# PHOTODIODE.net
KiCad netlist of a schematic drawn in Altium Designer
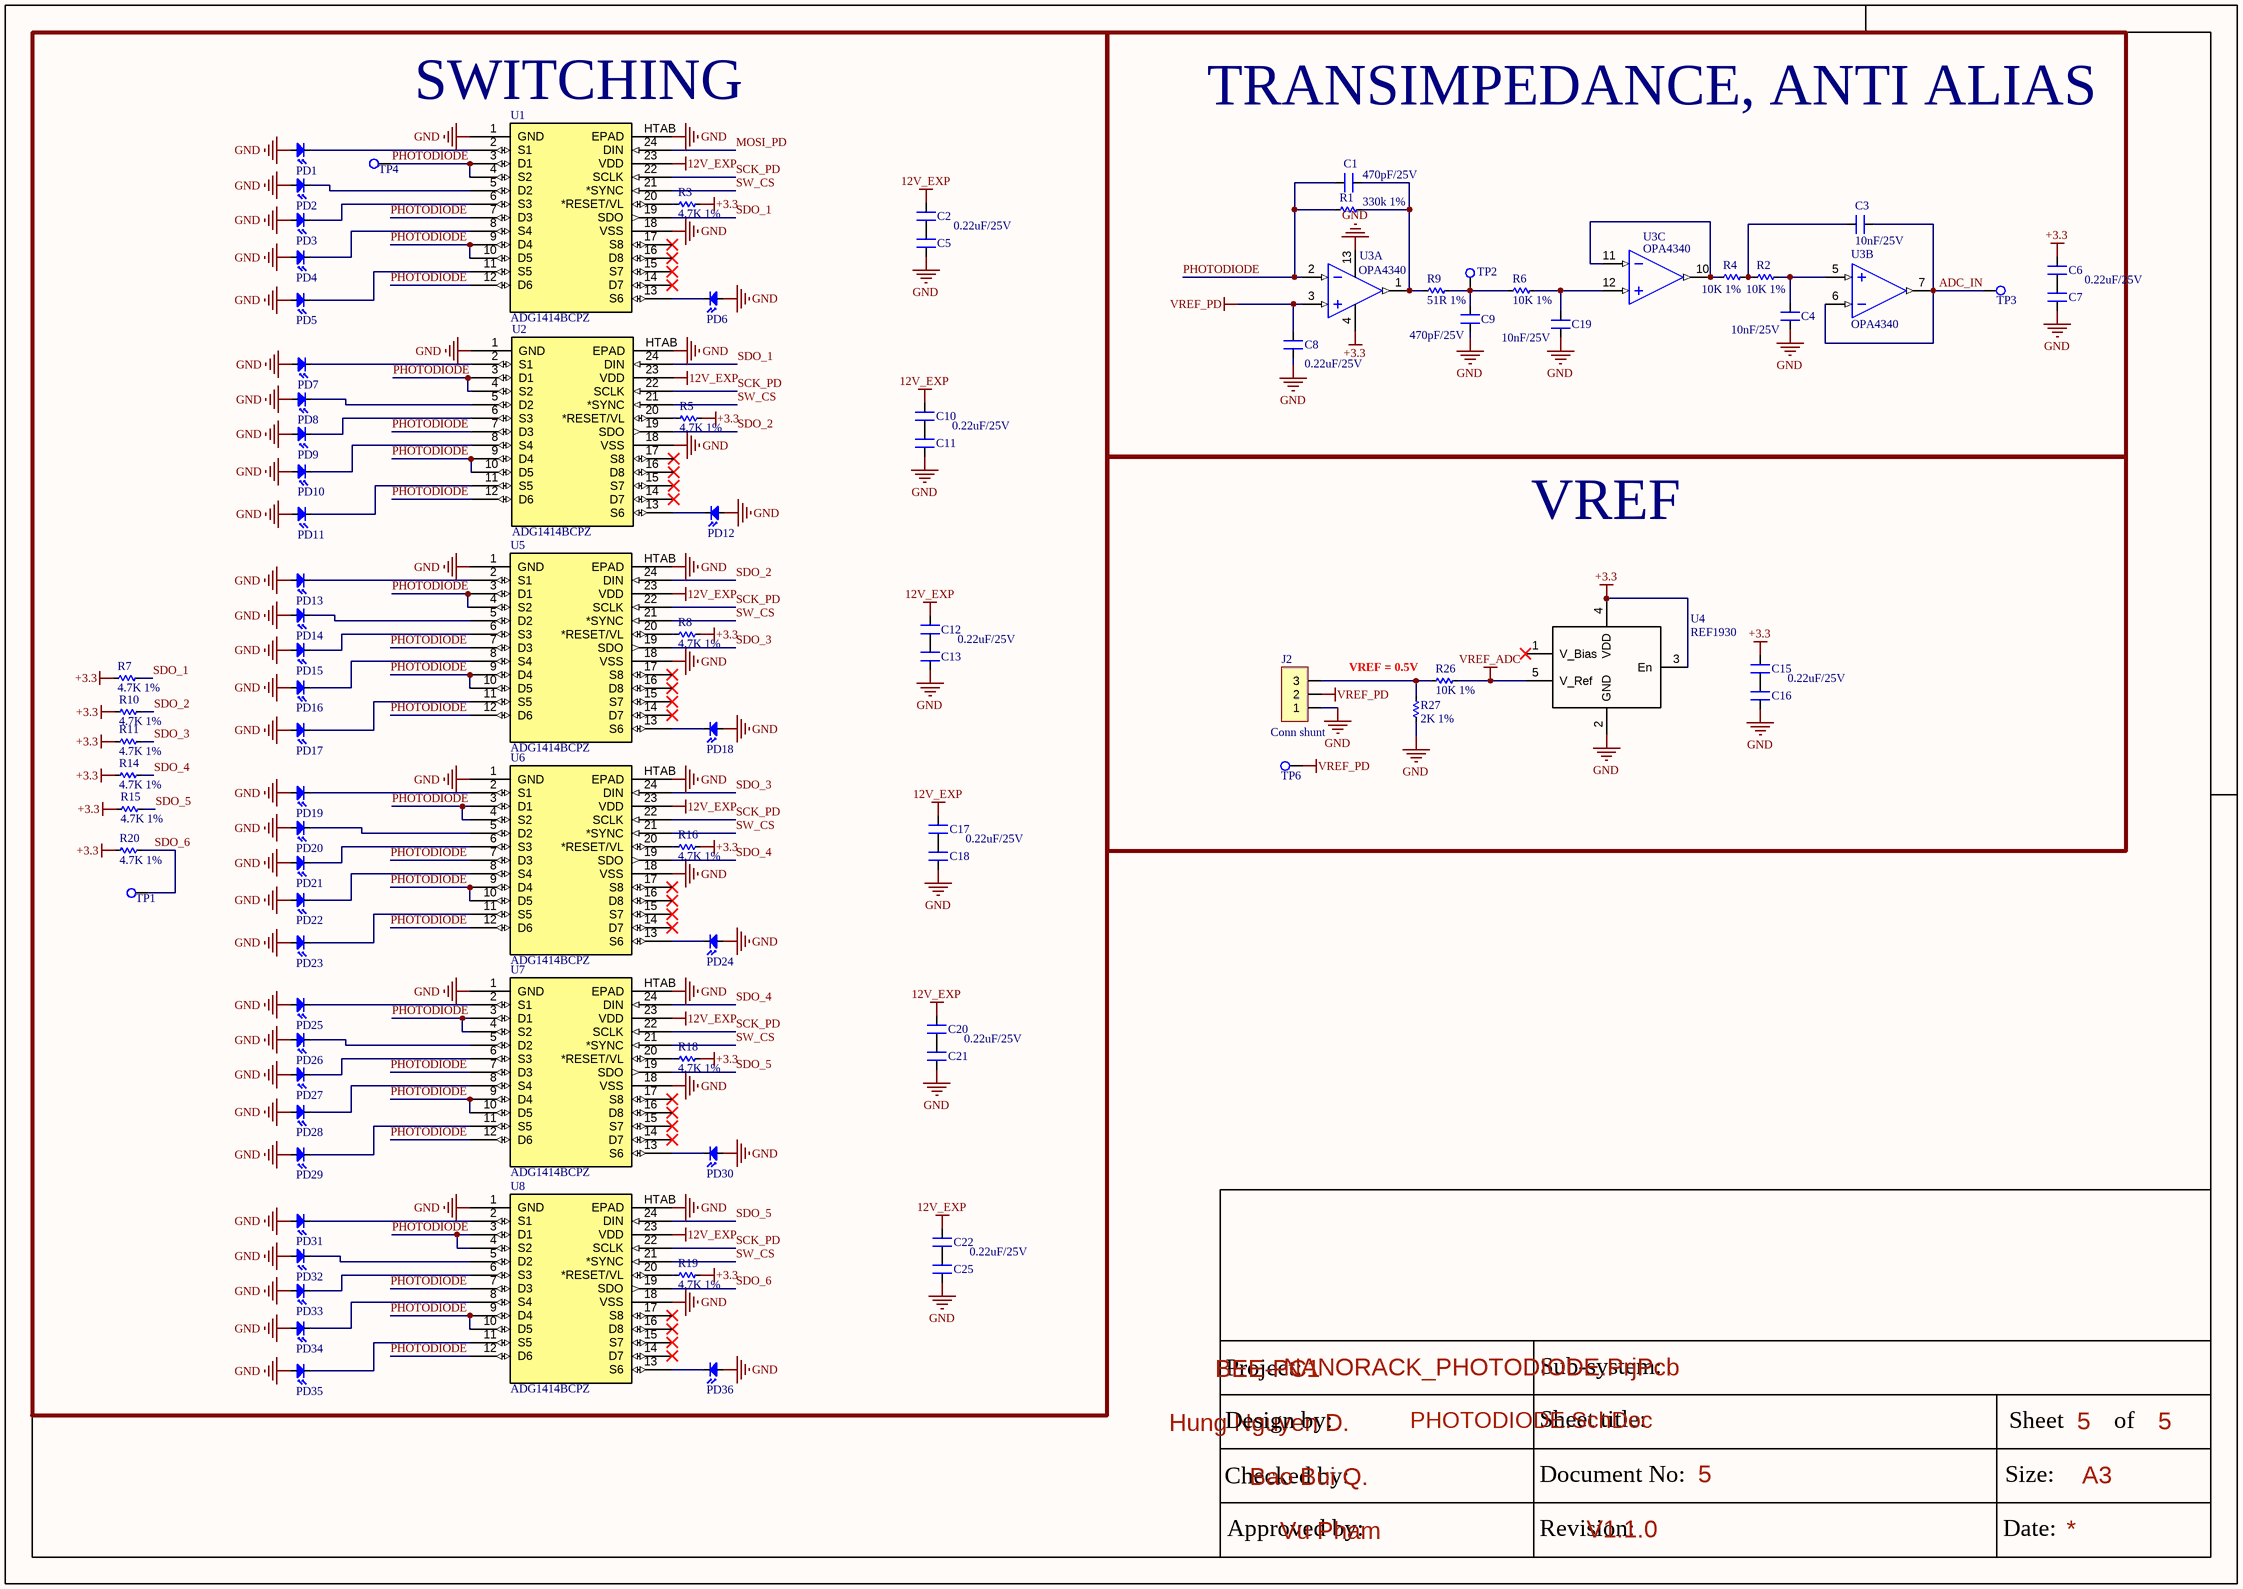
[diagram p0: PHOTODIODE.SchDoc]

(export (version "E")
  (design (tool "Eeschema 10.0.6"))
  (components
    (comp (ref "C1")
      (value "470pF/25V")
      (footprint "CN-SMD-0603")
      (description "0603")
      (libsource (lib "Capacitors") (part "CM"))
    )
    (comp (ref "C2")
      (value "0.22uF/25V")
      (footprint "CN-SMD-0603")
      (description "0603")
      (libsource (lib "Capacitors") (part "CM"))
    )
    (comp (ref "C3")
      (value "10nF/25V")
      (footprint "CN-SMD-0603")
      (description "0603")
      (libsource (lib "Capacitors") (part "CM"))
    )
    (comp (ref "C4")
      (value "10nF/25V")
      (footprint "CN-SMD-0603")
      (description "0603")
      (libsource (lib "Capacitors") (part "CM"))
    )
    (comp (ref "C5")
      (value "0.22uF/25V")
      (footprint "CN-SMD-0603")
      (description "0603")
      (libsource (lib "Capacitors") (part "CM"))
    )
    (comp (ref "C6")
      (value "0.22uF/25V")
      (footprint "CN-SMD-0603")
      (description "0603")
      (libsource (lib "Capacitors") (part "CM"))
    )
    (comp (ref "C7")
      (value "0.22uF/25V")
      (footprint "CN-SMD-0603")
      (description "0603")
      (libsource (lib "Capacitors") (part "CM"))
    )
    (comp (ref "C8")
      (value "0.22uF/25V")
      (footprint "CN-SMD-0603")
      (description "0603")
      (libsource (lib "Capacitors") (part "CM"))
    )
    (comp (ref "C9")
      (value "470pF/25V")
      (footprint "CN-SMD-0603")
      (description "0603")
      (libsource (lib "Capacitors") (part "CM"))
    )
    (comp (ref "C10")
      (value "0.22uF/25V")
      (footprint "CN-SMD-0603")
      (description "0603")
      (libsource (lib "Capacitors") (part "CM"))
    )
    (comp (ref "C11")
      (value "0.22uF/25V")
      (footprint "CN-SMD-0603")
      (description "0603")
      (libsource (lib "Capacitors") (part "CM"))
    )
    (comp (ref "C12")
      (value "0.22uF/25V")
      (footprint "CN-SMD-0603")
      (description "0603")
      (libsource (lib "Capacitors") (part "CM"))
    )
    (comp (ref "C13")
      (value "0.22uF/25V")
      (footprint "CN-SMD-0603")
      (description "0603")
      (libsource (lib "Capacitors") (part "CM"))
    )
    (comp (ref "C15")
      (value "0.22uF/25V")
      (footprint "CN-SMD-0603")
      (description "0603")
      (libsource (lib "Capacitors") (part "CM"))
    )
    (comp (ref "C16")
      (value "0.22uF/25V")
      (footprint "CN-SMD-0603")
      (description "0603")
      (libsource (lib "Capacitors") (part "CM"))
    )
    (comp (ref "C17")
      (value "0.22uF/25V")
      (footprint "CN-SMD-0603")
      (description "0603")
      (libsource (lib "Capacitors") (part "CM"))
    )
    (comp (ref "C18")
      (value "0.22uF/25V")
      (footprint "CN-SMD-0603")
      (description "0603")
      (libsource (lib "Capacitors") (part "CM"))
    )
    (comp (ref "C19")
      (value "10nF/25V")
      (footprint "CN-SMD-0603")
      (description "0603")
      (libsource (lib "Capacitors") (part "CM"))
    )
    (comp (ref "C20")
      (value "0.22uF/25V")
      (footprint "CN-SMD-0603")
      (description "0603")
      (libsource (lib "Capacitors") (part "CM"))
    )
    (comp (ref "C21")
      (value "0.22uF/25V")
      (footprint "CN-SMD-0603")
      (description "0603")
      (libsource (lib "Capacitors") (part "CM"))
    )
    (comp (ref "C22")
      (value "0.22uF/25V")
      (footprint "CN-SMD-0603")
      (description "0603")
      (libsource (lib "Capacitors") (part "CM"))
    )
    (comp (ref "C25")
      (value "0.22uF/25V")
      (footprint "CN-SMD-0603")
      (description "0603")
      (libsource (lib "Capacitors") (part "CM"))
    )
    (comp (ref "J2")
      (value "Conn shunt")
      (footprint "M50-3930342")
      (description "WR-PHD 2.54 mm Angled Socket Header")
      (fields
        (field (name "MANUFACTURER") "Würth Elektronik eiSos GmbH")
        (field (name "PARTNO") "613003143121")
        (field (name "CREATED BY") "Karrer Zheng")
      )
      (libsource (lib "Library") (part "JP3"))
    )
    (comp (ref "PD1")
      (value "Photodiode")
      (footprint "VEMD5080X01")
      (libsource (lib "Library_HUNG") (part "Photodiode"))
    )
    (comp (ref "PD2")
      (value "Photodiode")
      (footprint "VEMD5080X01")
      (libsource (lib "Library_HUNG") (part "Photodiode"))
    )
    (comp (ref "PD3")
      (value "Photodiode")
      (footprint "VEMD5080X01")
      (libsource (lib "Library_HUNG") (part "Photodiode"))
    )
    (comp (ref "PD4")
      (value "Photodiode")
      (footprint "VEMD5080X01")
      (libsource (lib "Library_HUNG") (part "Photodiode"))
    )
    (comp (ref "PD5")
      (value "Photodiode")
      (footprint "VEMD5080X01")
      (libsource (lib "Library_HUNG") (part "Photodiode"))
    )
    (comp (ref "PD6")
      (value "Photodiode")
      (footprint "VEMD5080X01")
      (libsource (lib "Library_HUNG") (part "Photodiode"))
    )
    (comp (ref "PD7")
      (value "Photodiode")
      (footprint "VEMD5080X01")
      (libsource (lib "Library_HUNG") (part "Photodiode"))
    )
    (comp (ref "PD8")
      (value "Photodiode")
      (footprint "VEMD5080X01")
      (libsource (lib "Library_HUNG") (part "Photodiode"))
    )
    (comp (ref "PD9")
      (value "Photodiode")
      (footprint "VEMD5080X01")
      (libsource (lib "Library_HUNG") (part "Photodiode"))
    )
    (comp (ref "PD10")
      (value "Photodiode")
      (footprint "VEMD5080X01")
      (libsource (lib "Library_HUNG") (part "Photodiode"))
    )
    (comp (ref "PD11")
      (value "Photodiode")
      (footprint "VEMD5080X01")
      (libsource (lib "Library_HUNG") (part "Photodiode"))
    )
    (comp (ref "PD12")
      (value "Photodiode")
      (footprint "VEMD5080X01")
      (libsource (lib "Library_HUNG") (part "Photodiode"))
    )
    (comp (ref "PD13")
      (value "Photodiode")
      (footprint "VEMD5080X01")
      (libsource (lib "Library_HUNG") (part "Photodiode"))
    )
    (comp (ref "PD14")
      (value "Photodiode")
      (footprint "VEMD5080X01")
      (libsource (lib "Library_HUNG") (part "Photodiode"))
    )
    (comp (ref "PD15")
      (value "Photodiode")
      (footprint "VEMD5080X01")
      (libsource (lib "Library_HUNG") (part "Photodiode"))
    )
    (comp (ref "PD16")
      (value "Photodiode")
      (footprint "VEMD5080X01")
      (libsource (lib "Library_HUNG") (part "Photodiode"))
    )
    (comp (ref "PD17")
      (value "Photodiode")
      (footprint "VEMD5080X01")
      (libsource (lib "Library_HUNG") (part "Photodiode"))
    )
    (comp (ref "PD18")
      (value "Photodiode")
      (footprint "VEMD5080X01")
      (libsource (lib "Library_HUNG") (part "Photodiode"))
    )
    (comp (ref "PD19")
      (value "Photodiode")
      (footprint "VEMD5080X01")
      (libsource (lib "Library_HUNG") (part "Photodiode"))
    )
    (comp (ref "PD20")
      (value "Photodiode")
      (footprint "VEMD5080X01")
      (libsource (lib "Library_HUNG") (part "Photodiode"))
    )
    (comp (ref "PD21")
      (value "Photodiode")
      (footprint "VEMD5080X01")
      (libsource (lib "Library_HUNG") (part "Photodiode"))
    )
    (comp (ref "PD22")
      (value "Photodiode")
      (footprint "VEMD5080X01")
      (libsource (lib "Library_HUNG") (part "Photodiode"))
    )
    (comp (ref "PD23")
      (value "Photodiode")
      (footprint "VEMD5080X01")
      (libsource (lib "Library_HUNG") (part "Photodiode"))
    )
    (comp (ref "PD24")
      (value "Photodiode")
      (footprint "VEMD5080X01")
      (libsource (lib "Library_HUNG") (part "Photodiode"))
    )
    (comp (ref "PD25")
      (value "Photodiode")
      (footprint "VEMD5080X01")
      (libsource (lib "Library_HUNG") (part "Photodiode"))
    )
    (comp (ref "PD26")
      (value "Photodiode")
      (footprint "VEMD5080X01")
      (libsource (lib "Library_HUNG") (part "Photodiode"))
    )
    (comp (ref "PD27")
      (value "Photodiode")
      (footprint "VEMD5080X01")
      (libsource (lib "Library_HUNG") (part "Photodiode"))
    )
    (comp (ref "PD28")
      (value "Photodiode")
      (footprint "VEMD5080X01")
      (libsource (lib "Library_HUNG") (part "Photodiode"))
    )
    (comp (ref "PD29")
      (value "Photodiode")
      (footprint "VEMD5080X01")
      (libsource (lib "Library_HUNG") (part "Photodiode"))
    )
    (comp (ref "PD30")
      (value "Photodiode")
      (footprint "VEMD5080X01")
      (libsource (lib "Library_HUNG") (part "Photodiode"))
    )
    (comp (ref "PD31")
      (value "Photodiode")
      (footprint "VEMD5080X01")
      (libsource (lib "Library_HUNG") (part "Photodiode"))
    )
    (comp (ref "PD32")
      (value "Photodiode")
      (footprint "VEMD5080X01")
      (libsource (lib "Library_HUNG") (part "Photodiode"))
    )
    (comp (ref "PD33")
      (value "Photodiode")
      (footprint "VEMD5080X01")
      (libsource (lib "Library_HUNG") (part "Photodiode"))
    )
    (comp (ref "PD34")
      (value "Photodiode")
      (footprint "VEMD5080X01")
      (libsource (lib "Library_HUNG") (part "Photodiode"))
    )
    (comp (ref "PD35")
      (value "Photodiode")
      (footprint "VEMD5080X01")
      (libsource (lib "Library_HUNG") (part "Photodiode"))
    )
    (comp (ref "PD36")
      (value "Photodiode")
      (footprint "VEMD5080X01")
      (libsource (lib "Library_HUNG") (part "Photodiode"))
    )
    (comp (ref "R1")
      (value "330k 1%")
      (footprint "RES-SMD-0603")
      (description "0603")
      (fields
        (field (name "MANUFACTURER") "Generic Components")
        (field (name "PUBLISHER") "Altium Hobart Technology Centre")
      )
      (libsource (lib "Library") (part "Res-SMD"))
    )
    (comp (ref "R2")
      (value "10K 1%")
      (footprint "RES-SMD-0603")
      (description "0603")
      (fields
        (field (name "MANUFACTURER") "Generic Components")
        (field (name "PUBLISHER") "Altium Hobart Technology Centre")
      )
      (libsource (lib "Library") (part "Res-SMD"))
    )
    (comp (ref "R3")
      (value "4.7K 1%")
      (footprint "RES-SMD-0603")
      (description "0603")
      (fields
        (field (name "MANUFACTURER") "Generic Components")
        (field (name "PUBLISHER") "Altium Hobart Technology Centre")
      )
      (libsource (lib "Library") (part "Res-SMD"))
    )
    (comp (ref "R4")
      (value "10K 1%")
      (footprint "RES-SMD-0603")
      (description "0603")
      (fields
        (field (name "MANUFACTURER") "Generic Components")
        (field (name "PUBLISHER") "Altium Hobart Technology Centre")
      )
      (libsource (lib "Library") (part "Res-SMD"))
    )
    (comp (ref "R5")
      (value "4.7K 1%")
      (footprint "RES-SMD-0603")
      (description "0603")
      (fields
        (field (name "MANUFACTURER") "Generic Components")
        (field (name "PUBLISHER") "Altium Hobart Technology Centre")
      )
      (libsource (lib "Library") (part "Res-SMD"))
    )
    (comp (ref "R6")
      (value "10K 1%")
      (footprint "RES-SMD-0603")
      (description "0603")
      (fields
        (field (name "MANUFACTURER") "Generic Components")
        (field (name "PUBLISHER") "Altium Hobart Technology Centre")
      )
      (libsource (lib "Library") (part "Res-SMD"))
    )
    (comp (ref "R7")
      (value "4.7K 1%")
      (footprint "RES-SMD-0603")
      (description "0603")
      (fields
        (field (name "MANUFACTURER") "Generic Components")
        (field (name "PUBLISHER") "Altium Hobart Technology Centre")
      )
      (libsource (lib "Library") (part "Res-SMD"))
    )
    (comp (ref "R8")
      (value "4.7K 1%")
      (footprint "RES-SMD-0603")
      (description "0603")
      (fields
        (field (name "MANUFACTURER") "Generic Components")
        (field (name "PUBLISHER") "Altium Hobart Technology Centre")
      )
      (libsource (lib "Library") (part "Res-SMD"))
    )
    (comp (ref "R9")
      (value "51R 1%")
      (footprint "RES-SMD-0603")
      (description "0603")
      (fields
        (field (name "MANUFACTURER") "Generic Components")
        (field (name "PUBLISHER") "Altium Hobart Technology Centre")
      )
      (libsource (lib "Library") (part "Res-SMD"))
    )
    (comp (ref "R10")
      (value "4.7K 1%")
      (footprint "RES-SMD-0603")
      (description "0603")
      (fields
        (field (name "MANUFACTURER") "Generic Components")
        (field (name "PUBLISHER") "Altium Hobart Technology Centre")
      )
      (libsource (lib "Library") (part "Res-SMD"))
    )
    (comp (ref "R11")
      (value "4.7K 1%")
      (footprint "RES-SMD-0603")
      (description "0603")
      (fields
        (field (name "MANUFACTURER") "Generic Components")
        (field (name "PUBLISHER") "Altium Hobart Technology Centre")
      )
      (libsource (lib "Library") (part "Res-SMD"))
    )
    (comp (ref "R14")
      (value "4.7K 1%")
      (footprint "RES-SMD-0603")
      (description "0603")
      (fields
        (field (name "MANUFACTURER") "Generic Components")
        (field (name "PUBLISHER") "Altium Hobart Technology Centre")
      )
      (libsource (lib "Library") (part "Res-SMD"))
    )
    (comp (ref "R15")
      (value "4.7K 1%")
      (footprint "RES-SMD-0603")
      (description "0603")
      (fields
        (field (name "MANUFACTURER") "Generic Components")
        (field (name "PUBLISHER") "Altium Hobart Technology Centre")
      )
      (libsource (lib "Library") (part "Res-SMD"))
    )
    (comp (ref "R16")
      (value "4.7K 1%")
      (footprint "RES-SMD-0603")
      (description "0603")
      (fields
        (field (name "MANUFACTURER") "Generic Components")
        (field (name "PUBLISHER") "Altium Hobart Technology Centre")
      )
      (libsource (lib "Library") (part "Res-SMD"))
    )
    (comp (ref "R18")
      (value "4.7K 1%")
      (footprint "RES-SMD-0603")
      (description "0603")
      (fields
        (field (name "MANUFACTURER") "Generic Components")
        (field (name "PUBLISHER") "Altium Hobart Technology Centre")
      )
      (libsource (lib "Library") (part "Res-SMD"))
    )
    (comp (ref "R19")
      (value "4.7K 1%")
      (footprint "RES-SMD-0603")
      (description "0603")
      (fields
        (field (name "MANUFACTURER") "Generic Components")
        (field (name "PUBLISHER") "Altium Hobart Technology Centre")
      )
      (libsource (lib "Library") (part "Res-SMD"))
    )
    (comp (ref "R20")
      (value "4.7K 1%")
      (footprint "RES-SMD-0603")
      (description "0603")
      (fields
        (field (name "MANUFACTURER") "Generic Components")
        (field (name "PUBLISHER") "Altium Hobart Technology Centre")
      )
      (libsource (lib "Library") (part "Res-SMD"))
    )
    (comp (ref "R26")
      (value "10K 1%")
      (footprint "RES-SMD-0603")
      (description "0603")
      (fields
        (field (name "MANUFACTURER") "Generic Components")
        (field (name "PUBLISHER") "Altium Hobart Technology Centre")
      )
      (libsource (lib "Library") (part "Res-SMD"))
    )
    (comp (ref "R27")
      (value "2K 1%")
      (footprint "RES-SMD-0603")
      (description "0603")
      (fields
        (field (name "MANUFACTURER") "Generic Components")
        (field (name "PUBLISHER") "Altium Hobart Technology Centre")
      )
      (libsource (lib "Library") (part "Res-SMD"))
    )
    (comp (ref "TP1")
      (value "Test_Point")
      (footprint "TESTPOINT")
      (libsource (lib "Library_HUNG") (part "Test_Point"))
    )
    (comp (ref "TP2")
      (value "Test_Point")
      (footprint "TESTPOINT")
      (libsource (lib "Library_HUNG") (part "Test_Point"))
    )
    (comp (ref "TP3")
      (value "Test_Point")
      (footprint "TESTPOINT")
      (libsource (lib "Library_HUNG") (part "Test_Point"))
    )
    (comp (ref "TP4")
      (value "Test_Point")
      (footprint "TESTPOINT")
      (libsource (lib "Library_HUNG") (part "Test_Point"))
    )
    (comp (ref "TP6")
      (value "Test_Point")
      (footprint "TESTPOINT")
      (libsource (lib "Library_HUNG") (part "Test_Point"))
    )
    (comp (ref "U1")
      (value "ADG1414BCPZ")
      (footprint "ADG1414BCPZ")
      (description "IC SW SPST-NOX8 11.5OHM 24LFCSP")
      (libsource (lib "Library_HUNG") (part "ADG1414"))
    )
    (comp (ref "U2")
      (value "ADG1414BCPZ")
      (footprint "ADG1414BCPZ")
      (description "IC SW SPST-NOX8 11.5OHM 24LFCSP")
      (libsource (lib "Library_HUNG") (part "ADG1414"))
    )
    (comp (ref "U3")
      (value "OPA4340")
      (footprint "SSOP16")
      (description "IC CMOS 4 CIRCUIT 16SSOP")
      (libsource (lib "Library") (part "OPA4340"))
    )
    (comp (ref "U4")
      (value "REF1930")
      (footprint "SOT23-5")
      (description "REF1941AIDDCT")
      (libsource (lib "Library") (part "REF19xx"))
    )
    (comp (ref "U5")
      (value "ADG1414BCPZ")
      (footprint "ADG1414BCPZ")
      (description "IC SW SPST-NOX8 11.5OHM 24LFCSP")
      (libsource (lib "Library_HUNG") (part "ADG1414"))
    )
    (comp (ref "U6")
      (value "ADG1414BCPZ")
      (footprint "ADG1414BCPZ")
      (description "IC SW SPST-NOX8 11.5OHM 24LFCSP")
      (libsource (lib "Library_HUNG") (part "ADG1414"))
    )
    (comp (ref "U7")
      (value "ADG1414BCPZ")
      (footprint "ADG1414BCPZ")
      (description "IC SW SPST-NOX8 11.5OHM 24LFCSP")
      (libsource (lib "Library_HUNG") (part "ADG1414"))
    )
    (comp (ref "U8")
      (value "ADG1414BCPZ")
      (footprint "ADG1414BCPZ")
      (description "IC SW SPST-NOX8 11.5OHM 24LFCSP")
      (libsource (lib "Library_HUNG") (part "ADG1414"))
    )
  )
  (nets
    (net (code "1") (name "+3.3") (class "Default")
      (node (ref "C15") (pin "2") (pinfunction "2_2") (pintype "passive"))
      (node (ref "C6") (pin "2") (pinfunction "2_2") (pintype "passive"))
      (node (ref "R10") (pin "2") (pinfunction "2_2") (pintype "passive"))
      (node (ref "R11") (pin "2") (pinfunction "2_2") (pintype "passive"))
      (node (ref "R14") (pin "2") (pinfunction "2_2") (pintype "passive"))
      (node (ref "R15") (pin "2") (pinfunction "2_2") (pintype "passive"))
      (node (ref "R16") (pin "2") (pinfunction "2_2") (pintype "passive"))
      (node (ref "R18") (pin "2") (pinfunction "2_2") (pintype "passive"))
      (node (ref "R19") (pin "2") (pinfunction "2_2") (pintype "passive"))
      (node (ref "R20") (pin "2") (pinfunction "2_2") (pintype "passive"))
      (node (ref "R3") (pin "2") (pinfunction "2_2") (pintype "passive"))
      (node (ref "R5") (pin "2") (pinfunction "2_2") (pintype "passive"))
      (node (ref "R7") (pin "2") (pinfunction "2_2") (pintype "passive"))
      (node (ref "R8") (pin "2") (pinfunction "2_2") (pintype "passive"))
      (node (ref "U3") (pin "4") (pinfunction "+V_4") (pintype "passive"))
      (node (ref "U4") (pin "3") (pinfunction "En_3") (pintype "passive"))
      (node (ref "U4") (pin "4") (pinfunction "VDD_4") (pintype "passive"))
    )
    (net (code "2") (name "/ADC_IN") (class "Default")
      (node (ref "C3") (pin "1") (pinfunction "1_1") (pintype "passive"))
      (node (ref "TP3") (pin "1") (pintype "power_in"))
      (node (ref "U3") (pin "6") (pinfunction "IN-_6") (pintype "input"))
      (node (ref "U3") (pin "7") (pinfunction "OUT_7") (pintype "output"))
    )
    (net (code "3") (name "/MOSI_PD") (class "Default")
      (node (ref "U1") (pin "24") (pinfunction "DIN_24") (pintype "input"))
    )
    (net (code "4") (name "/PHOTODIODE") (class "Default")
      (node (ref "C1") (pin "1") (pinfunction "1_1") (pintype "passive"))
      (node (ref "R1") (pin "1") (pinfunction "1_1") (pintype "passive"))
      (node (ref "TP4") (pin "1") (pintype "power_in"))
      (node (ref "U1") (pin "10") (pinfunction "D5_10") (pintype "bidirectional"))
      (node (ref "U1") (pin "12") (pinfunction "D6_12") (pintype "bidirectional"))
      (node (ref "U1") (pin "3") (pinfunction "D1_3") (pintype "bidirectional"))
      (node (ref "U1") (pin "4") (pinfunction "S2_4") (pintype "bidirectional"))
      (node (ref "U1") (pin "7") (pinfunction "D3_7") (pintype "bidirectional"))
      (node (ref "U1") (pin "9") (pinfunction "D4_9") (pintype "bidirectional"))
      (node (ref "U2") (pin "10") (pinfunction "D5_10") (pintype "bidirectional"))
      (node (ref "U2") (pin "12") (pinfunction "D6_12") (pintype "bidirectional"))
      (node (ref "U2") (pin "3") (pinfunction "D1_3") (pintype "bidirectional"))
      (node (ref "U2") (pin "4") (pinfunction "S2_4") (pintype "bidirectional"))
      (node (ref "U2") (pin "7") (pinfunction "D3_7") (pintype "bidirectional"))
      (node (ref "U2") (pin "9") (pinfunction "D4_9") (pintype "bidirectional"))
      (node (ref "U3") (pin "2") (pinfunction "IN-_2") (pintype "input"))
      (node (ref "U5") (pin "10") (pinfunction "D5_10") (pintype "bidirectional"))
      (node (ref "U5") (pin "12") (pinfunction "D6_12") (pintype "bidirectional"))
      (node (ref "U5") (pin "3") (pinfunction "D1_3") (pintype "bidirectional"))
      (node (ref "U5") (pin "4") (pinfunction "S2_4") (pintype "bidirectional"))
      (node (ref "U5") (pin "7") (pinfunction "D3_7") (pintype "bidirectional"))
      (node (ref "U5") (pin "9") (pinfunction "D4_9") (pintype "bidirectional"))
      (node (ref "U6") (pin "10") (pinfunction "D5_10") (pintype "bidirectional"))
      (node (ref "U6") (pin "12") (pinfunction "D6_12") (pintype "bidirectional"))
      (node (ref "U6") (pin "3") (pinfunction "D1_3") (pintype "bidirectional"))
      (node (ref "U6") (pin "4") (pinfunction "S2_4") (pintype "bidirectional"))
      (node (ref "U6") (pin "7") (pinfunction "D3_7") (pintype "bidirectional"))
      (node (ref "U6") (pin "9") (pinfunction "D4_9") (pintype "bidirectional"))
      (node (ref "U7") (pin "10") (pinfunction "D5_10") (pintype "bidirectional"))
      (node (ref "U7") (pin "12") (pinfunction "D6_12") (pintype "bidirectional"))
      (node (ref "U7") (pin "3") (pinfunction "D1_3") (pintype "bidirectional"))
      (node (ref "U7") (pin "4") (pinfunction "S2_4") (pintype "bidirectional"))
      (node (ref "U7") (pin "7") (pinfunction "D3_7") (pintype "bidirectional"))
      (node (ref "U7") (pin "9") (pinfunction "D4_9") (pintype "bidirectional"))
      (node (ref "U8") (pin "10") (pinfunction "D5_10") (pintype "bidirectional"))
      (node (ref "U8") (pin "12") (pinfunction "D6_12") (pintype "bidirectional"))
      (node (ref "U8") (pin "3") (pinfunction "D1_3") (pintype "bidirectional"))
      (node (ref "U8") (pin "4") (pinfunction "S2_4") (pintype "bidirectional"))
      (node (ref "U8") (pin "7") (pinfunction "D3_7") (pintype "bidirectional"))
      (node (ref "U8") (pin "9") (pinfunction "D4_9") (pintype "bidirectional"))
    )
    (net (code "5") (name "/SCK_PD") (class "Default")
      (node (ref "U1") (pin "22") (pinfunction "SCLK_22") (pintype "input"))
      (node (ref "U2") (pin "22") (pinfunction "SCLK_22") (pintype "input"))
      (node (ref "U5") (pin "22") (pinfunction "SCLK_22") (pintype "input"))
      (node (ref "U6") (pin "22") (pinfunction "SCLK_22") (pintype "input"))
      (node (ref "U7") (pin "22") (pinfunction "SCLK_22") (pintype "input"))
      (node (ref "U8") (pin "22") (pinfunction "SCLK_22") (pintype "input"))
    )
    (net (code "6") (name "/SDO_1") (class "Default")
      (node (ref "R7") (pin "1") (pinfunction "1_1") (pintype "passive"))
      (node (ref "U1") (pin "19") (pinfunction "SDO_19") (pintype "output"))
      (node (ref "U2") (pin "24") (pinfunction "DIN_24") (pintype "input"))
    )
    (net (code "7") (name "/SDO_2") (class "Default")
      (node (ref "R10") (pin "1") (pinfunction "1_1") (pintype "passive"))
      (node (ref "U2") (pin "19") (pinfunction "SDO_19") (pintype "output"))
      (node (ref "U5") (pin "24") (pinfunction "DIN_24") (pintype "input"))
    )
    (net (code "8") (name "/SDO_3") (class "Default")
      (node (ref "R11") (pin "1") (pinfunction "1_1") (pintype "passive"))
      (node (ref "U5") (pin "19") (pinfunction "SDO_19") (pintype "output"))
      (node (ref "U6") (pin "24") (pinfunction "DIN_24") (pintype "input"))
    )
    (net (code "9") (name "/SDO_4") (class "Default")
      (node (ref "R14") (pin "1") (pinfunction "1_1") (pintype "passive"))
      (node (ref "U6") (pin "19") (pinfunction "SDO_19") (pintype "output"))
      (node (ref "U7") (pin "24") (pinfunction "DIN_24") (pintype "input"))
    )
    (net (code "10") (name "/SDO_5") (class "Default")
      (node (ref "R15") (pin "1") (pinfunction "1_1") (pintype "passive"))
      (node (ref "U7") (pin "19") (pinfunction "SDO_19") (pintype "output"))
      (node (ref "U8") (pin "24") (pinfunction "DIN_24") (pintype "input"))
    )
    (net (code "11") (name "/SDO_6") (class "Default")
      (node (ref "R20") (pin "1") (pinfunction "1_1") (pintype "passive"))
      (node (ref "TP1") (pin "1") (pintype "power_in"))
      (node (ref "U8") (pin "19") (pinfunction "SDO_19") (pintype "output"))
    )
    (net (code "12") (name "/SW_CS") (class "Default")
      (node (ref "U1") (pin "21") (pinfunction "*SYNC_21") (pintype "input"))
      (node (ref "U2") (pin "21") (pinfunction "*SYNC_21") (pintype "input"))
      (node (ref "U5") (pin "21") (pinfunction "*SYNC_21") (pintype "input"))
      (node (ref "U6") (pin "21") (pinfunction "*SYNC_21") (pintype "input"))
      (node (ref "U7") (pin "21") (pinfunction "*SYNC_21") (pintype "input"))
      (node (ref "U8") (pin "21") (pinfunction "*SYNC_21") (pintype "input"))
    )
    (net (code "13") (name "12V_EXP") (class "Default")
      (node (ref "C10") (pin "2") (pinfunction "2_2") (pintype "passive"))
      (node (ref "C12") (pin "2") (pinfunction "2_2") (pintype "passive"))
      (node (ref "C17") (pin "2") (pinfunction "2_2") (pintype "passive"))
      (node (ref "C2") (pin "2") (pinfunction "2_2") (pintype "passive"))
      (node (ref "C20") (pin "2") (pinfunction "2_2") (pintype "passive"))
      (node (ref "C22") (pin "2") (pinfunction "2_2") (pintype "passive"))
      (node (ref "U1") (pin "23") (pinfunction "VDD_23") (pintype "power_in"))
      (node (ref "U2") (pin "23") (pinfunction "VDD_23") (pintype "power_in"))
      (node (ref "U5") (pin "23") (pinfunction "VDD_23") (pintype "power_in"))
      (node (ref "U6") (pin "23") (pinfunction "VDD_23") (pintype "power_in"))
      (node (ref "U7") (pin "23") (pinfunction "VDD_23") (pintype "power_in"))
      (node (ref "U8") (pin "23") (pinfunction "VDD_23") (pintype "power_in"))
    )
    (net (code "14") (name "GND") (class "Default")
      (node (ref "C11") (pin "1") (pinfunction "1_1") (pintype "passive"))
      (node (ref "C13") (pin "1") (pinfunction "1_1") (pintype "passive"))
      (node (ref "C16") (pin "1") (pinfunction "1_1") (pintype "passive"))
      (node (ref "C18") (pin "1") (pinfunction "1_1") (pintype "passive"))
      (node (ref "C19") (pin "1") (pinfunction "1_1") (pintype "passive"))
      (node (ref "C21") (pin "1") (pinfunction "1_1") (pintype "passive"))
      (node (ref "C25") (pin "1") (pinfunction "1_1") (pintype "passive"))
      (node (ref "C4") (pin "1") (pinfunction "1_1") (pintype "passive"))
      (node (ref "C5") (pin "1") (pinfunction "1_1") (pintype "passive"))
      (node (ref "C7") (pin "1") (pinfunction "1_1") (pintype "passive"))
      (node (ref "C8") (pin "1") (pinfunction "1_1") (pintype "passive"))
      (node (ref "C9") (pin "1") (pinfunction "1_1") (pintype "passive"))
      (node (ref "J2") (pin "1") (pinfunction "1_1") (pintype "passive"))
      (node (ref "PD1") (pin "1") (pinfunction "A_1") (pintype "passive"))
      (node (ref "PD10") (pin "1") (pinfunction "A_1") (pintype "passive"))
      (node (ref "PD11") (pin "1") (pinfunction "A_1") (pintype "passive"))
      (node (ref "PD12") (pin "1") (pinfunction "A_1") (pintype "passive"))
      (node (ref "PD13") (pin "1") (pinfunction "A_1") (pintype "passive"))
      (node (ref "PD14") (pin "1") (pinfunction "A_1") (pintype "passive"))
      (node (ref "PD15") (pin "1") (pinfunction "A_1") (pintype "passive"))
      (node (ref "PD16") (pin "1") (pinfunction "A_1") (pintype "passive"))
      (node (ref "PD17") (pin "1") (pinfunction "A_1") (pintype "passive"))
      (node (ref "PD18") (pin "1") (pinfunction "A_1") (pintype "passive"))
      (node (ref "PD19") (pin "1") (pinfunction "A_1") (pintype "passive"))
      (node (ref "PD2") (pin "1") (pinfunction "A_1") (pintype "passive"))
      (node (ref "PD20") (pin "1") (pinfunction "A_1") (pintype "passive"))
      (node (ref "PD21") (pin "1") (pinfunction "A_1") (pintype "passive"))
      (node (ref "PD22") (pin "1") (pinfunction "A_1") (pintype "passive"))
      (node (ref "PD23") (pin "1") (pinfunction "A_1") (pintype "passive"))
      (node (ref "PD24") (pin "1") (pinfunction "A_1") (pintype "passive"))
      (node (ref "PD25") (pin "1") (pinfunction "A_1") (pintype "passive"))
      (node (ref "PD26") (pin "1") (pinfunction "A_1") (pintype "passive"))
      (node (ref "PD27") (pin "1") (pinfunction "A_1") (pintype "passive"))
      (node (ref "PD28") (pin "1") (pinfunction "A_1") (pintype "passive"))
      (node (ref "PD29") (pin "1") (pinfunction "A_1") (pintype "passive"))
      (node (ref "PD3") (pin "1") (pinfunction "A_1") (pintype "passive"))
      (node (ref "PD30") (pin "1") (pinfunction "A_1") (pintype "passive"))
      (node (ref "PD31") (pin "1") (pinfunction "A_1") (pintype "passive"))
      (node (ref "PD32") (pin "1") (pinfunction "A_1") (pintype "passive"))
      (node (ref "PD33") (pin "1") (pinfunction "A_1") (pintype "passive"))
      (node (ref "PD34") (pin "1") (pinfunction "A_1") (pintype "passive"))
      (node (ref "PD35") (pin "1") (pinfunction "A_1") (pintype "passive"))
      (node (ref "PD36") (pin "1") (pinfunction "A_1") (pintype "passive"))
      (node (ref "PD4") (pin "1") (pinfunction "A_1") (pintype "passive"))
      (node (ref "PD5") (pin "1") (pinfunction "A_1") (pintype "passive"))
      (node (ref "PD6") (pin "1") (pinfunction "A_1") (pintype "passive"))
      (node (ref "PD7") (pin "1") (pinfunction "A_1") (pintype "passive"))
      (node (ref "PD8") (pin "1") (pinfunction "A_1") (pintype "passive"))
      (node (ref "PD9") (pin "1") (pinfunction "A_1") (pintype "passive"))
      (node (ref "R27") (pin "1") (pinfunction "1_1") (pintype "passive"))
      (node (ref "U1") (pin "1") (pinfunction "GND_1") (pintype "power_in"))
      (node (ref "U1") (pin "18") (pinfunction "VSS_18") (pintype "power_in"))
      (node (ref "U1") (pin "HTAB") (pinfunction "EPAD_HTAB") (pintype "passive"))
      (node (ref "U2") (pin "1") (pinfunction "GND_1") (pintype "power_in"))
      (node (ref "U2") (pin "18") (pinfunction "VSS_18") (pintype "power_in"))
      (node (ref "U2") (pin "HTAB") (pinfunction "EPAD_HTAB") (pintype "passive"))
      (node (ref "U3") (pin "13") (pinfunction "-V_13") (pintype "passive"))
      (node (ref "U4") (pin "2") (pinfunction "GND_2") (pintype "passive"))
      (node (ref "U5") (pin "1") (pinfunction "GND_1") (pintype "power_in"))
      (node (ref "U5") (pin "18") (pinfunction "VSS_18") (pintype "power_in"))
      (node (ref "U5") (pin "HTAB") (pinfunction "EPAD_HTAB") (pintype "passive"))
      (node (ref "U6") (pin "1") (pinfunction "GND_1") (pintype "power_in"))
      (node (ref "U6") (pin "18") (pinfunction "VSS_18") (pintype "power_in"))
      (node (ref "U6") (pin "HTAB") (pinfunction "EPAD_HTAB") (pintype "passive"))
      (node (ref "U7") (pin "1") (pinfunction "GND_1") (pintype "power_in"))
      (node (ref "U7") (pin "18") (pinfunction "VSS_18") (pintype "power_in"))
      (node (ref "U7") (pin "HTAB") (pinfunction "EPAD_HTAB") (pintype "passive"))
      (node (ref "U8") (pin "1") (pinfunction "GND_1") (pintype "power_in"))
      (node (ref "U8") (pin "18") (pinfunction "VSS_18") (pintype "power_in"))
      (node (ref "U8") (pin "HTAB") (pinfunction "EPAD_HTAB") (pintype "passive"))
    )
    (net (code "15") (name "Net-(C2-Pad1)") (class "Default")
      (node (ref "C2") (pin "1") (pinfunction "1_1") (pintype "passive"))
      (node (ref "C5") (pin "2") (pinfunction "2_2") (pintype "passive"))
    )
    (net (code "16") (name "Net-(C3-Pad2)") (class "Default")
      (node (ref "C3") (pin "2") (pinfunction "2_2") (pintype "passive"))
      (node (ref "R2") (pin "1") (pinfunction "1_1") (pintype "passive"))
      (node (ref "R4") (pin "2") (pinfunction "2_2") (pintype "passive"))
    )
    (net (code "17") (name "Net-(C6-Pad1)") (class "Default")
      (node (ref "C6") (pin "1") (pinfunction "1_1") (pintype "passive"))
      (node (ref "C7") (pin "2") (pinfunction "2_2") (pintype "passive"))
    )
    (net (code "18") (name "Net-(C9-Pad2)") (class "Default")
      (node (ref "C9") (pin "2") (pinfunction "2_2") (pintype "passive"))
      (node (ref "R6") (pin "1") (pinfunction "1_1") (pintype "passive"))
      (node (ref "R9") (pin "2") (pinfunction "2_2") (pintype "passive"))
      (node (ref "TP2") (pin "1") (pintype "power_in"))
    )
    (net (code "19") (name "Net-(C10-Pad1)") (class "Default")
      (node (ref "C10") (pin "1") (pinfunction "1_1") (pintype "passive"))
      (node (ref "C11") (pin "2") (pinfunction "2_2") (pintype "passive"))
    )
    (net (code "20") (name "Net-(C12-Pad1)") (class "Default")
      (node (ref "C12") (pin "1") (pinfunction "1_1") (pintype "passive"))
      (node (ref "C13") (pin "2") (pinfunction "2_2") (pintype "passive"))
    )
    (net (code "21") (name "Net-(C15-Pad1)") (class "Default")
      (node (ref "C15") (pin "1") (pinfunction "1_1") (pintype "passive"))
      (node (ref "C16") (pin "2") (pinfunction "2_2") (pintype "passive"))
    )
    (net (code "22") (name "Net-(C17-Pad1)") (class "Default")
      (node (ref "C17") (pin "1") (pinfunction "1_1") (pintype "passive"))
      (node (ref "C18") (pin "2") (pinfunction "2_2") (pintype "passive"))
    )
    (net (code "23") (name "Net-(C20-Pad1)") (class "Default")
      (node (ref "C20") (pin "1") (pinfunction "1_1") (pintype "passive"))
      (node (ref "C21") (pin "2") (pinfunction "2_2") (pintype "passive"))
    )
    (net (code "24") (name "Net-(C22-Pad1)") (class "Default")
      (node (ref "C22") (pin "1") (pinfunction "1_1") (pintype "passive"))
      (node (ref "C25") (pin "2") (pinfunction "2_2") (pintype "passive"))
    )
    (net (code "25") (name "Net-(J2-Pad3)") (class "Default")
      (node (ref "J2") (pin "3") (pinfunction "3_3") (pintype "passive"))
      (node (ref "R26") (pin "2") (pinfunction "2_2") (pintype "passive"))
      (node (ref "R27") (pin "2") (pinfunction "2_2") (pintype "passive"))
    )
    (net (code "26") (name "Net-(PD1-K)") (class "Default")
      (node (ref "PD1") (pin "2") (pinfunction "K_2") (pintype "passive"))
      (node (ref "U1") (pin "2") (pinfunction "S1_2") (pintype "bidirectional"))
    )
    (net (code "27") (name "Net-(PD2-K)") (class "Default")
      (node (ref "PD2") (pin "2") (pinfunction "K_2") (pintype "passive"))
      (node (ref "U1") (pin "5") (pinfunction "D2_5") (pintype "bidirectional"))
    )
    (net (code "28") (name "Net-(PD3-K)") (class "Default")
      (node (ref "PD3") (pin "2") (pinfunction "K_2") (pintype "passive"))
      (node (ref "U1") (pin "6") (pinfunction "S3_6") (pintype "bidirectional"))
    )
    (net (code "29") (name "Net-(PD4-K)") (class "Default")
      (node (ref "PD4") (pin "2") (pinfunction "K_2") (pintype "passive"))
      (node (ref "U1") (pin "8") (pinfunction "S4_8") (pintype "bidirectional"))
    )
    (net (code "30") (name "Net-(PD5-K)") (class "Default")
      (node (ref "PD5") (pin "2") (pinfunction "K_2") (pintype "passive"))
      (node (ref "U1") (pin "11") (pinfunction "S5_11") (pintype "bidirectional"))
    )
    (net (code "31") (name "Net-(PD6-K)") (class "Default")
      (node (ref "PD6") (pin "2") (pinfunction "K_2") (pintype "passive"))
      (node (ref "U1") (pin "13") (pinfunction "S6_13") (pintype "bidirectional"))
    )
    (net (code "32") (name "Net-(PD7-K)") (class "Default")
      (node (ref "PD7") (pin "2") (pinfunction "K_2") (pintype "passive"))
      (node (ref "U2") (pin "2") (pinfunction "S1_2") (pintype "bidirectional"))
    )
    (net (code "33") (name "Net-(PD8-K)") (class "Default")
      (node (ref "PD8") (pin "2") (pinfunction "K_2") (pintype "passive"))
      (node (ref "U2") (pin "5") (pinfunction "D2_5") (pintype "bidirectional"))
    )
    (net (code "34") (name "Net-(PD9-K)") (class "Default")
      (node (ref "PD9") (pin "2") (pinfunction "K_2") (pintype "passive"))
      (node (ref "U2") (pin "6") (pinfunction "S3_6") (pintype "bidirectional"))
    )
    (net (code "35") (name "Net-(PD10-K)") (class "Default")
      (node (ref "PD10") (pin "2") (pinfunction "K_2") (pintype "passive"))
      (node (ref "U2") (pin "8") (pinfunction "S4_8") (pintype "bidirectional"))
    )
    (net (code "36") (name "Net-(PD11-K)") (class "Default")
      (node (ref "PD11") (pin "2") (pinfunction "K_2") (pintype "passive"))
      (node (ref "U2") (pin "11") (pinfunction "S5_11") (pintype "bidirectional"))
    )
    (net (code "37") (name "Net-(PD12-K)") (class "Default")
      (node (ref "PD12") (pin "2") (pinfunction "K_2") (pintype "passive"))
      (node (ref "U2") (pin "13") (pinfunction "S6_13") (pintype "bidirectional"))
    )
    (net (code "38") (name "Net-(PD13-K)") (class "Default")
      (node (ref "PD13") (pin "2") (pinfunction "K_2") (pintype "passive"))
      (node (ref "U5") (pin "2") (pinfunction "S1_2") (pintype "bidirectional"))
    )
    (net (code "39") (name "Net-(PD14-K)") (class "Default")
      (node (ref "PD14") (pin "2") (pinfunction "K_2") (pintype "passive"))
      (node (ref "U5") (pin "5") (pinfunction "D2_5") (pintype "bidirectional"))
    )
    (net (code "40") (name "Net-(PD15-K)") (class "Default")
      (node (ref "PD15") (pin "2") (pinfunction "K_2") (pintype "passive"))
      (node (ref "U5") (pin "6") (pinfunction "S3_6") (pintype "bidirectional"))
    )
    (net (code "41") (name "Net-(PD16-K)") (class "Default")
      (node (ref "PD16") (pin "2") (pinfunction "K_2") (pintype "passive"))
      (node (ref "U5") (pin "8") (pinfunction "S4_8") (pintype "bidirectional"))
    )
    (net (code "42") (name "Net-(PD17-K)") (class "Default")
      (node (ref "PD17") (pin "2") (pinfunction "K_2") (pintype "passive"))
      (node (ref "U5") (pin "11") (pinfunction "S5_11") (pintype "bidirectional"))
    )
    (net (code "43") (name "Net-(PD18-K)") (class "Default")
      (node (ref "PD18") (pin "2") (pinfunction "K_2") (pintype "passive"))
      (node (ref "U5") (pin "13") (pinfunction "S6_13") (pintype "bidirectional"))
    )
    (net (code "44") (name "Net-(PD19-K)") (class "Default")
      (node (ref "PD19") (pin "2") (pinfunction "K_2") (pintype "passive"))
      (node (ref "U6") (pin "2") (pinfunction "S1_2") (pintype "bidirectional"))
    )
    (net (code "45") (name "Net-(PD20-K)") (class "Default")
      (node (ref "PD20") (pin "2") (pinfunction "K_2") (pintype "passive"))
      (node (ref "U6") (pin "5") (pinfunction "D2_5") (pintype "bidirectional"))
    )
    (net (code "46") (name "Net-(PD21-K)") (class "Default")
      (node (ref "PD21") (pin "2") (pinfunction "K_2") (pintype "passive"))
      (node (ref "U6") (pin "6") (pinfunction "S3_6") (pintype "bidirectional"))
    )
    (net (code "47") (name "Net-(PD22-K)") (class "Default")
      (node (ref "PD22") (pin "2") (pinfunction "K_2") (pintype "passive"))
      (node (ref "U6") (pin "8") (pinfunction "S4_8") (pintype "bidirectional"))
    )
    (net (code "48") (name "Net-(PD23-K)") (class "Default")
      (node (ref "PD23") (pin "2") (pinfunction "K_2") (pintype "passive"))
      (node (ref "U6") (pin "11") (pinfunction "S5_11") (pintype "bidirectional"))
    )
    (net (code "49") (name "Net-(PD24-K)") (class "Default")
      (node (ref "PD24") (pin "2") (pinfunction "K_2") (pintype "passive"))
      (node (ref "U6") (pin "13") (pinfunction "S6_13") (pintype "bidirectional"))
    )
    (net (code "50") (name "Net-(PD25-K)") (class "Default")
      (node (ref "PD25") (pin "2") (pinfunction "K_2") (pintype "passive"))
      (node (ref "U7") (pin "2") (pinfunction "S1_2") (pintype "bidirectional"))
    )
    (net (code "51") (name "Net-(PD26-K)") (class "Default")
      (node (ref "PD26") (pin "2") (pinfunction "K_2") (pintype "passive"))
      (node (ref "U7") (pin "5") (pinfunction "D2_5") (pintype "bidirectional"))
    )
    (net (code "52") (name "Net-(PD27-K)") (class "Default")
      (node (ref "PD27") (pin "2") (pinfunction "K_2") (pintype "passive"))
      (node (ref "U7") (pin "6") (pinfunction "S3_6") (pintype "bidirectional"))
    )
    (net (code "53") (name "Net-(PD28-K)") (class "Default")
      (node (ref "PD28") (pin "2") (pinfunction "K_2") (pintype "passive"))
      (node (ref "U7") (pin "8") (pinfunction "S4_8") (pintype "bidirectional"))
    )
    (net (code "54") (name "Net-(PD29-K)") (class "Default")
      (node (ref "PD29") (pin "2") (pinfunction "K_2") (pintype "passive"))
      (node (ref "U7") (pin "11") (pinfunction "S5_11") (pintype "bidirectional"))
    )
    (net (code "55") (name "Net-(PD30-K)") (class "Default")
      (node (ref "PD30") (pin "2") (pinfunction "K_2") (pintype "passive"))
      (node (ref "U7") (pin "13") (pinfunction "S6_13") (pintype "bidirectional"))
    )
    (net (code "56") (name "Net-(PD31-K)") (class "Default")
      (node (ref "PD31") (pin "2") (pinfunction "K_2") (pintype "passive"))
      (node (ref "U8") (pin "2") (pinfunction "S1_2") (pintype "bidirectional"))
    )
    (net (code "57") (name "Net-(PD32-K)") (class "Default")
      (node (ref "PD32") (pin "2") (pinfunction "K_2") (pintype "passive"))
      (node (ref "U8") (pin "5") (pinfunction "D2_5") (pintype "bidirectional"))
    )
    (net (code "58") (name "Net-(PD33-K)") (class "Default")
      (node (ref "PD33") (pin "2") (pinfunction "K_2") (pintype "passive"))
      (node (ref "U8") (pin "6") (pinfunction "S3_6") (pintype "bidirectional"))
    )
    (net (code "59") (name "Net-(PD34-K)") (class "Default")
      (node (ref "PD34") (pin "2") (pinfunction "K_2") (pintype "passive"))
      (node (ref "U8") (pin "8") (pinfunction "S4_8") (pintype "bidirectional"))
    )
    (net (code "60") (name "Net-(PD35-K)") (class "Default")
      (node (ref "PD35") (pin "2") (pinfunction "K_2") (pintype "passive"))
      (node (ref "U8") (pin "11") (pinfunction "S5_11") (pintype "bidirectional"))
    )
    (net (code "61") (name "Net-(PD36-K)") (class "Default")
      (node (ref "PD36") (pin "2") (pinfunction "K_2") (pintype "passive"))
      (node (ref "U8") (pin "13") (pinfunction "S6_13") (pintype "bidirectional"))
    )
    (net (code "62") (name "Net-(U1-*RESET{slash}VL)") (class "Default")
      (node (ref "R3") (pin "1") (pinfunction "1_1") (pintype "passive"))
      (node (ref "U1") (pin "20") (pinfunction "*RESET/VL_20") (pintype "bidirectional"))
    )
    (net (code "63") (name "Net-(U2-*RESET{slash}VL)") (class "Default")
      (node (ref "R5") (pin "1") (pinfunction "1_1") (pintype "passive"))
      (node (ref "U2") (pin "20") (pinfunction "*RESET/VL_20") (pintype "bidirectional"))
    )
    (net (code "64") (name "Net-(U3A-OUT)") (class "Default")
      (node (ref "C1") (pin "2") (pinfunction "2_2") (pintype "passive"))
      (node (ref "R1") (pin "2") (pinfunction "2_2") (pintype "passive"))
      (node (ref "R9") (pin "1") (pinfunction "1_1") (pintype "passive"))
      (node (ref "U3") (pin "1") (pinfunction "OUT_1") (pintype "output"))
    )
    (net (code "65") (name "Net-(U3B-IN+)") (class "Default")
      (node (ref "C4") (pin "2") (pinfunction "2_2") (pintype "passive"))
      (node (ref "R2") (pin "2") (pinfunction "2_2") (pintype "passive"))
      (node (ref "U3") (pin "5") (pinfunction "IN+_5") (pintype "input"))
    )
    (net (code "66") (name "Net-(U3C-IN+)") (class "Default")
      (node (ref "C19") (pin "2") (pinfunction "2_2") (pintype "passive"))
      (node (ref "R6") (pin "2") (pinfunction "2_2") (pintype "passive"))
      (node (ref "U3") (pin "12") (pinfunction "IN+_12") (pintype "input"))
    )
    (net (code "67") (name "Net-(U3C-IN-)") (class "Default")
      (node (ref "R4") (pin "1") (pinfunction "1_1") (pintype "passive"))
      (node (ref "U3") (pin "10") (pinfunction "OUT_10") (pintype "output"))
      (node (ref "U3") (pin "11") (pinfunction "IN-_11") (pintype "input"))
    )
    (net (code "68") (name "Net-(U5-*RESET{slash}VL)") (class "Default")
      (node (ref "R8") (pin "1") (pinfunction "1_1") (pintype "passive"))
      (node (ref "U5") (pin "20") (pinfunction "*RESET/VL_20") (pintype "bidirectional"))
    )
    (net (code "69") (name "Net-(U6-*RESET{slash}VL)") (class "Default")
      (node (ref "R16") (pin "1") (pinfunction "1_1") (pintype "passive"))
      (node (ref "U6") (pin "20") (pinfunction "*RESET/VL_20") (pintype "bidirectional"))
    )
    (net (code "70") (name "Net-(U7-*RESET{slash}VL)") (class "Default")
      (node (ref "R18") (pin "1") (pinfunction "1_1") (pintype "passive"))
      (node (ref "U7") (pin "20") (pinfunction "*RESET/VL_20") (pintype "bidirectional"))
    )
    (net (code "71") (name "Net-(U8-*RESET{slash}VL)") (class "Default")
      (node (ref "R19") (pin "1") (pinfunction "1_1") (pintype "passive"))
      (node (ref "U8") (pin "20") (pinfunction "*RESET/VL_20") (pintype "bidirectional"))
    )
    (net (code "72") (name "VREF_ADC") (class "Default")
      (node (ref "R26") (pin "1") (pinfunction "1_1") (pintype "passive"))
      (node (ref "U4") (pin "5") (pinfunction "V_Ref_5") (pintype "passive"))
    )
    (net (code "73") (name "VREF_PD") (class "Default")
      (node (ref "C8") (pin "2") (pinfunction "2_2") (pintype "passive"))
      (node (ref "J2") (pin "2") (pinfunction "2_2") (pintype "passive"))
      (node (ref "TP6") (pin "1") (pintype "power_in"))
      (node (ref "U3") (pin "3") (pinfunction "IN+_3") (pintype "input"))
    )
    (net (code "74") (name "unconnected-(U1-D7-Pad14)") (class "Default")
      (node (ref "U1") (pin "14") (pinfunction "D7_14") (pintype "bidirectional+no_connect"))
    )
    (net (code "75") (name "unconnected-(U1-D8-Pad16)") (class "Default")
      (node (ref "U1") (pin "16") (pinfunction "D8_16") (pintype "bidirectional+no_connect"))
    )
    (net (code "76") (name "unconnected-(U1-S7-Pad15)") (class "Default")
      (node (ref "U1") (pin "15") (pinfunction "S7_15") (pintype "bidirectional+no_connect"))
    )
    (net (code "77") (name "unconnected-(U1-S8-Pad17)") (class "Default")
      (node (ref "U1") (pin "17") (pinfunction "S8_17") (pintype "bidirectional+no_connect"))
    )
    (net (code "78") (name "unconnected-(U2-D7-Pad14)") (class "Default")
      (node (ref "U2") (pin "14") (pinfunction "D7_14") (pintype "bidirectional+no_connect"))
    )
    (net (code "79") (name "unconnected-(U2-D8-Pad16)") (class "Default")
      (node (ref "U2") (pin "16") (pinfunction "D8_16") (pintype "bidirectional+no_connect"))
    )
    (net (code "80") (name "unconnected-(U2-S7-Pad15)") (class "Default")
      (node (ref "U2") (pin "15") (pinfunction "S7_15") (pintype "bidirectional+no_connect"))
    )
    (net (code "81") (name "unconnected-(U2-S8-Pad17)") (class "Default")
      (node (ref "U2") (pin "17") (pinfunction "S8_17") (pintype "bidirectional+no_connect"))
    )
    (net (code "82") (name "unconnected-(U4-V_Bias-Pad1)") (class "Default")
      (node (ref "U4") (pin "1") (pinfunction "V_Bias_1") (pintype "passive+no_connect"))
    )
    (net (code "83") (name "unconnected-(U5-D7-Pad14)") (class "Default")
      (node (ref "U5") (pin "14") (pinfunction "D7_14") (pintype "bidirectional+no_connect"))
    )
    (net (code "84") (name "unconnected-(U5-D8-Pad16)") (class "Default")
      (node (ref "U5") (pin "16") (pinfunction "D8_16") (pintype "bidirectional+no_connect"))
    )
    (net (code "85") (name "unconnected-(U5-S7-Pad15)") (class "Default")
      (node (ref "U5") (pin "15") (pinfunction "S7_15") (pintype "bidirectional+no_connect"))
    )
    (net (code "86") (name "unconnected-(U5-S8-Pad17)") (class "Default")
      (node (ref "U5") (pin "17") (pinfunction "S8_17") (pintype "bidirectional+no_connect"))
    )
    (net (code "87") (name "unconnected-(U6-D7-Pad14)") (class "Default")
      (node (ref "U6") (pin "14") (pinfunction "D7_14") (pintype "bidirectional+no_connect"))
    )
    (net (code "88") (name "unconnected-(U6-D8-Pad16)") (class "Default")
      (node (ref "U6") (pin "16") (pinfunction "D8_16") (pintype "bidirectional+no_connect"))
    )
    (net (code "89") (name "unconnected-(U6-S7-Pad15)") (class "Default")
      (node (ref "U6") (pin "15") (pinfunction "S7_15") (pintype "bidirectional+no_connect"))
    )
    (net (code "90") (name "unconnected-(U6-S8-Pad17)") (class "Default")
      (node (ref "U6") (pin "17") (pinfunction "S8_17") (pintype "bidirectional+no_connect"))
    )
    (net (code "91") (name "unconnected-(U7-D7-Pad14)") (class "Default")
      (node (ref "U7") (pin "14") (pinfunction "D7_14") (pintype "bidirectional+no_connect"))
    )
    (net (code "92") (name "unconnected-(U7-D8-Pad16)") (class "Default")
      (node (ref "U7") (pin "16") (pinfunction "D8_16") (pintype "bidirectional+no_connect"))
    )
    (net (code "93") (name "unconnected-(U7-S7-Pad15)") (class "Default")
      (node (ref "U7") (pin "15") (pinfunction "S7_15") (pintype "bidirectional+no_connect"))
    )
    (net (code "94") (name "unconnected-(U7-S8-Pad17)") (class "Default")
      (node (ref "U7") (pin "17") (pinfunction "S8_17") (pintype "bidirectional+no_connect"))
    )
    (net (code "95") (name "unconnected-(U8-D7-Pad14)") (class "Default")
      (node (ref "U8") (pin "14") (pinfunction "D7_14") (pintype "bidirectional+no_connect"))
    )
    (net (code "96") (name "unconnected-(U8-D8-Pad16)") (class "Default")
      (node (ref "U8") (pin "16") (pinfunction "D8_16") (pintype "bidirectional+no_connect"))
    )
    (net (code "97") (name "unconnected-(U8-S7-Pad15)") (class "Default")
      (node (ref "U8") (pin "15") (pinfunction "S7_15") (pintype "bidirectional+no_connect"))
    )
    (net (code "98") (name "unconnected-(U8-S8-Pad17)") (class "Default")
      (node (ref "U8") (pin "17") (pinfunction "S8_17") (pintype "bidirectional+no_connect"))
    )
  )
)
